# Transmitter.net
KiCad netlist of a schematic drawn in Altium Designer
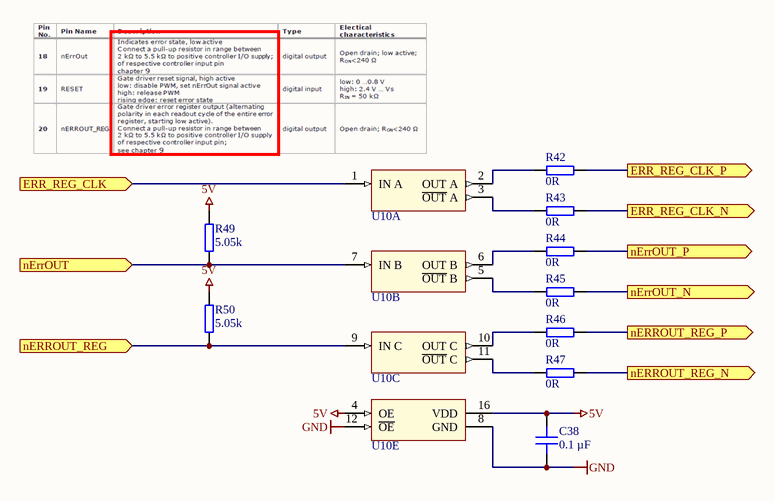
[diagram p0: Transmitter.SchDoc]

(export (version "E")
  (design (tool "Eeschema 10.0.6"))
  (components
    (comp (ref "C38")
      (value "0.1 µF")
      (footprint "C_0603")
      (description "Capacitor 0603, 50 VDC, 0.1 µF, X7R")
      (fields
        (field (name "MANUFACTURER PART NUMBER") "C0603X104K5RAC7411")
        (field (name "MANUFACTURER") "KEMET")
        (field (name "CREATED FROM") "MGremer")
      )
      (libsource (lib "user") (part "Capacitor"))
    )
    (comp (ref "R42")
      (value "0R")
      (footprint "RES 0603_1608")
      (description "SMD resistor E24 series")
      (fields
        (field (name "MANUFACTURER PART NUMBER") "RC0603JR-070RL")
        (field (name "MANUFACTURER") "YAGEO")
        (field (name "CREATED FROM") "MGremer")
      )
      (libsource (lib "user") (part "Resistor"))
    )
    (comp (ref "R43")
      (value "0R")
      (footprint "RES 0603_1608")
      (description "SMD resistor E24 series")
      (fields
        (field (name "MANUFACTURER PART NUMBER") "RC0603JR-070RL")
        (field (name "MANUFACTURER") "YAGEO")
        (field (name "CREATED FROM") "MGremer")
      )
      (libsource (lib "user") (part "Resistor"))
    )
    (comp (ref "R44")
      (value "0R")
      (footprint "RES 0603_1608")
      (description "SMD resistor E24 series")
      (fields
        (field (name "MANUFACTURER PART NUMBER") "RC0603JR-070RL")
        (field (name "MANUFACTURER") "YAGEO")
        (field (name "CREATED FROM") "MGremer")
      )
      (libsource (lib "user") (part "Resistor"))
    )
    (comp (ref "R45")
      (value "0R")
      (footprint "RES 0603_1608")
      (description "SMD resistor E24 series")
      (fields
        (field (name "MANUFACTURER PART NUMBER") "RC0603JR-070RL")
        (field (name "MANUFACTURER") "YAGEO")
        (field (name "CREATED FROM") "MGremer")
      )
      (libsource (lib "user") (part "Resistor"))
    )
    (comp (ref "R46")
      (value "0R")
      (footprint "RES 0603_1608")
      (description "SMD resistor E24 series")
      (fields
        (field (name "MANUFACTURER PART NUMBER") "RC0603JR-070RL")
        (field (name "MANUFACTURER") "YAGEO")
        (field (name "CREATED FROM") "MGremer")
      )
      (libsource (lib "user") (part "Resistor"))
    )
    (comp (ref "R47")
      (value "0R")
      (footprint "RES 0603_1608")
      (description "SMD resistor E24 series")
      (fields
        (field (name "MANUFACTURER PART NUMBER") "RC0603JR-070RL")
        (field (name "MANUFACTURER") "YAGEO")
        (field (name "CREATED FROM") "MGremer")
      )
      (libsource (lib "user") (part "Resistor"))
    )
    (comp (ref "R49")
      (value "5.05k")
      (footprint "RES 0603_1608")
      (description "SMD resistor 0.1%")
      (fields
        (field (name "MANUFACTURER PART NUMBER") "TNPW06035K05BEEA")
        (field (name "MANUFACTURER") "Vishay")
        (field (name "CREATED FROM") "DHufnagel")
      )
      (libsource (lib "user") (part "Resistor"))
    )
    (comp (ref "R50")
      (value "5.05k")
      (footprint "RES 0603_1608")
      (description "SMD resistor 0.1%")
      (fields
        (field (name "MANUFACTURER PART NUMBER") "TNPW06035K05BEEA")
        (field (name "MANUFACTURER") "Vishay")
        (field (name "CREATED FROM") "DHufnagel")
      )
      (libsource (lib "user") (part "Resistor"))
    )
    (comp (ref "U10")
      (value "DS26C31TMX/NOPB")
      (footprint "TI_D-R-PDSO-G16_N")
      (description "CMOS Quad Tri-State Differential Line Drivers, 16-pin Narrow SOIC, Pb-Free")
      (fields
        (field (name "MANUFACTURER") "Texas Instruments")
        (field (name "LCSC PART NUMBER") "C132085")
        (field (name "CREATED FROM") "T. Wendt")
      )
      (libsource (lib "user") (part "DS26C31TMX"))
    )
  )
  (nets
    (net (code "1") (name "/ERR_REG_CLK") (class "Default")
      (node (ref "U10") (pin "1") (pinfunction "IN_A_1") (pintype "input"))
    )
    (net (code "2") (name "/ERR_REG_CLK_N") (class "Default")
      (node (ref "R43") (pin "2") (pinfunction "2_2") (pintype "passive"))
    )
    (net (code "3") (name "/ERR_REG_CLK_P") (class "Default")
      (node (ref "R42") (pin "2") (pinfunction "2_2") (pintype "passive"))
    )
    (net (code "4") (name "/nERROUT_REG") (class "Default")
      (node (ref "R50") (pin "1") (pinfunction "1_1") (pintype "passive"))
      (node (ref "U10") (pin "9") (pinfunction "IN_C_9") (pintype "input"))
    )
    (net (code "5") (name "/nERROUT_REG_N") (class "Default")
      (node (ref "R47") (pin "2") (pinfunction "2_2") (pintype "passive"))
    )
    (net (code "6") (name "/nERROUT_REG_P") (class "Default")
      (node (ref "R46") (pin "2") (pinfunction "2_2") (pintype "passive"))
    )
    (net (code "7") (name "/nErrOUT") (class "Default")
      (node (ref "R49") (pin "1") (pinfunction "1_1") (pintype "passive"))
      (node (ref "U10") (pin "7") (pinfunction "IN_B_7") (pintype "input"))
    )
    (net (code "8") (name "/nErrOUT_N") (class "Default")
      (node (ref "R45") (pin "2") (pinfunction "2_2") (pintype "passive"))
    )
    (net (code "9") (name "/nErrOUT_P") (class "Default")
      (node (ref "R44") (pin "2") (pinfunction "2_2") (pintype "passive"))
    )
    (net (code "10") (name "5V") (class "Default")
      (node (ref "C38") (pin "2") (pinfunction "2_2") (pintype "passive"))
      (node (ref "R49") (pin "2") (pinfunction "2_2") (pintype "passive"))
      (node (ref "R50") (pin "2") (pinfunction "2_2") (pintype "passive"))
      (node (ref "U10") (pin "16") (pinfunction "VDD_16") (pintype "power_in"))
      (node (ref "U10") (pin "4") (pinfunction "OE_4") (pintype "input"))
    )
    (net (code "11") (name "GND") (class "Default")
      (node (ref "C38") (pin "1") (pinfunction "1_1") (pintype "passive"))
      (node (ref "U10") (pin "12") (pinfunction "~{OE}_12") (pintype "input"))
      (node (ref "U10") (pin "8") (pinfunction "GND_8") (pintype "power_in"))
    )
    (net (code "12") (name "Net-(U10A-OUT_A)") (class "Default")
      (node (ref "R42") (pin "1") (pinfunction "1_1") (pintype "passive"))
      (node (ref "U10") (pin "2") (pinfunction "OUT_A_2") (pintype "output"))
    )
    (net (code "13") (name "Net-(U10A-~{OUT}_A)") (class "Default")
      (node (ref "R43") (pin "1") (pinfunction "1_1") (pintype "passive"))
      (node (ref "U10") (pin "3") (pinfunction "~{OUT}_A_3") (pintype "output"))
    )
    (net (code "14") (name "Net-(U10B-OUT_B)") (class "Default")
      (node (ref "R44") (pin "1") (pinfunction "1_1") (pintype "passive"))
      (node (ref "U10") (pin "6") (pinfunction "OUT_B_6") (pintype "output"))
    )
    (net (code "15") (name "Net-(U10B-~{OUT}_B)") (class "Default")
      (node (ref "R45") (pin "1") (pinfunction "1_1") (pintype "passive"))
      (node (ref "U10") (pin "5") (pinfunction "~{OUT}_B_5") (pintype "output"))
    )
    (net (code "16") (name "Net-(U10C-OUT_C)") (class "Default")
      (node (ref "R46") (pin "1") (pinfunction "1_1") (pintype "passive"))
      (node (ref "U10") (pin "10") (pinfunction "OUT_C_10") (pintype "output"))
    )
    (net (code "17") (name "Net-(U10C-~{OUT}_C)") (class "Default")
      (node (ref "R47") (pin "1") (pinfunction "1_1") (pintype "passive"))
      (node (ref "U10") (pin "11") (pinfunction "~{OUT}_C_11") (pintype "output"))
    )
  )
)
